# powerboard.net
KiCad netlist of a schematic drawn in EAGLE
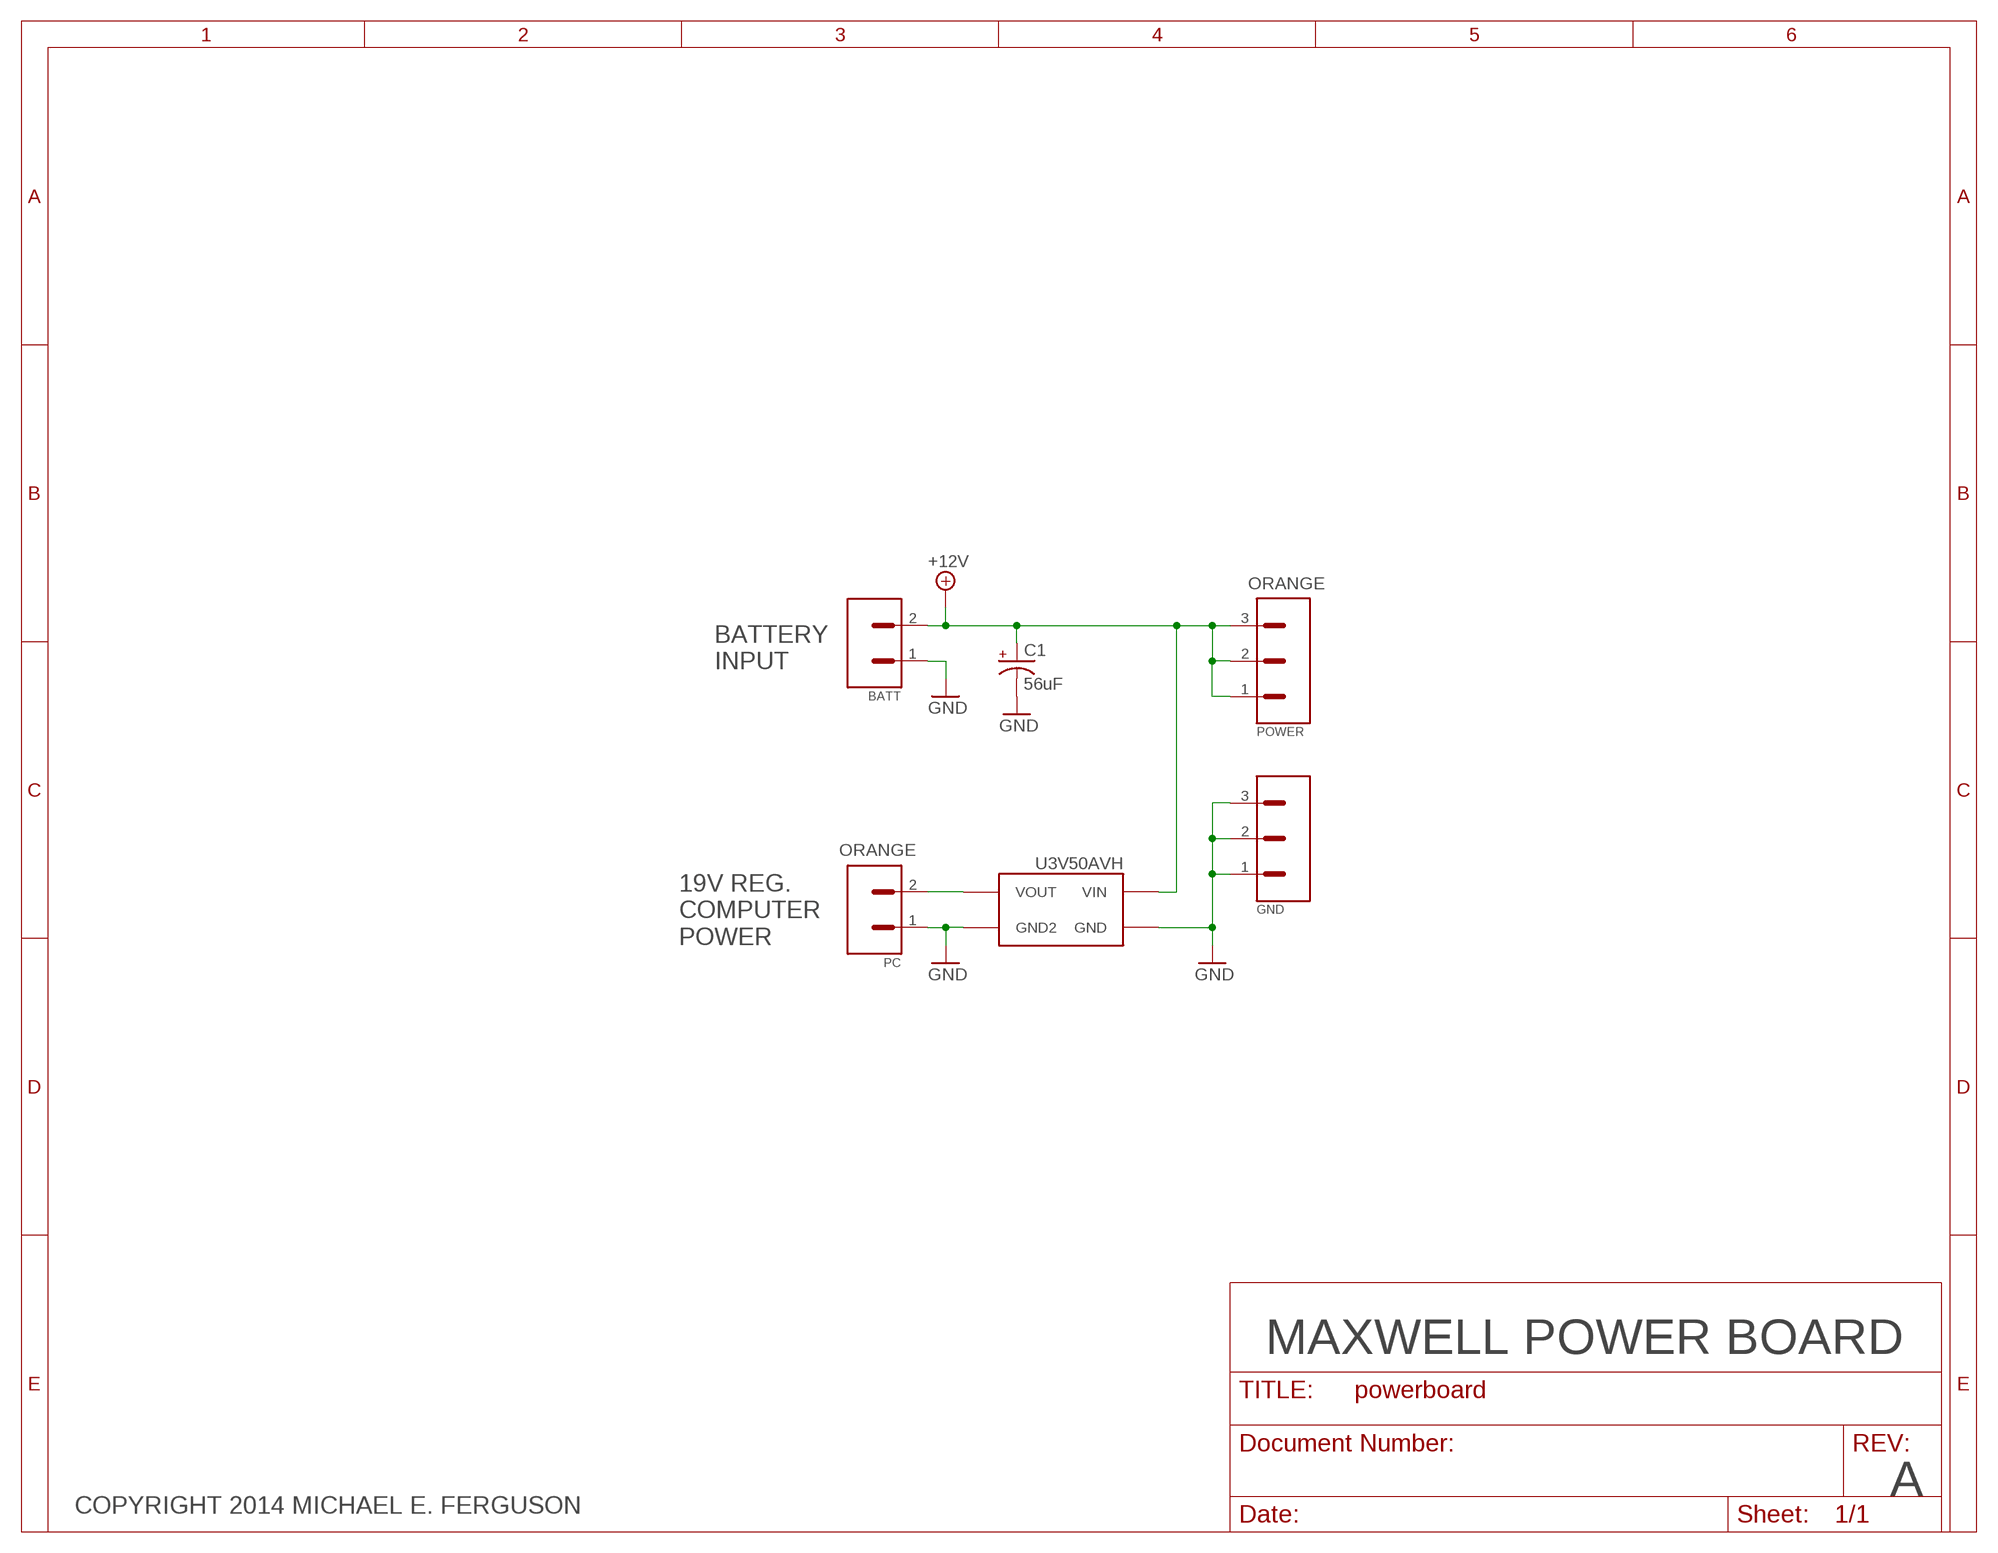
[diagram p0: schematic, sheet 1]

(export (version "E")
  (design (tool "Eeschema 10.0.6"))
  (components
    (comp (ref "BATT")
      (value "1760510000")
      (footprint "eagle-import:1760490000")
      (libsource (lib "eagle-import") (part "1760510000"))
    )
    (comp (ref "C1")
      (value "56uF")
      (footprint "eagle-import:OSCON_SVPF_6.3MM")
      (libsource (lib "eagle-import") (part "25SVPF56M"))
    )
    (comp (ref "GND")
      (value "1760520000")
      (footprint "eagle-import:1760520000")
      (libsource (lib "eagle-import") (part "1760520000"))
    )
    (comp (ref "PC")
      (value "1760490000")
      (footprint "eagle-import:1760490000")
      (libsource (lib "eagle-import") (part "1760490000"))
    )
    (comp (ref "POWER")
      (value "1760520000")
      (footprint "eagle-import:1760520000")
      (libsource (lib "eagle-import") (part "1760520000"))
    )
    (comp (ref "U3V50AVH")
      (value "U3V50AHV")
      (footprint "eagle-import:U3V50AHV")
      (libsource (lib "eagle-import") (part "U3V50AHV"))
    )
  )
  (nets
    (net (code "1") (name "+12V") (class "Default")
      (node (ref "BATT") (pin "2") (pinfunction "2_2") (pintype "bidirectional"))
      (node (ref "C1") (pin "+") (pinfunction "+_+") (pintype "passive"))
      (node (ref "POWER") (pin "1") (pinfunction "1_1") (pintype "bidirectional"))
      (node (ref "POWER") (pin "2") (pinfunction "2_2") (pintype "bidirectional"))
      (node (ref "POWER") (pin "3") (pinfunction "3_3") (pintype "bidirectional"))
      (node (ref "U3V50AVH") (pin "V_IN") (pinfunction "VIN_V_IN") (pintype "bidirectional"))
    )
    (net (code "2") (name "GND") (class "Default")
      (node (ref "BATT") (pin "1") (pinfunction "1_1") (pintype "bidirectional"))
      (node (ref "C1") (pin "-") (pinfunction "-_-") (pintype "passive"))
      (node (ref "GND") (pin "1") (pinfunction "1_1") (pintype "bidirectional"))
      (node (ref "GND") (pin "2") (pinfunction "2_2") (pintype "bidirectional"))
      (node (ref "GND") (pin "3") (pinfunction "3_3") (pintype "bidirectional"))
      (node (ref "PC") (pin "1") (pinfunction "1_1") (pintype "bidirectional"))
      (node (ref "U3V50AVH") (pin "GND_IN") (pinfunction "GND_GND_IN") (pintype "bidirectional"))
      (node (ref "U3V50AVH") (pin "GND_OUT") (pinfunction "GND2_GND_OUT") (pintype "bidirectional"))
    )
    (net (code "3") (name "Net-(U3V50AVH-VOUT)") (class "Default")
      (node (ref "PC") (pin "2") (pinfunction "2_2") (pintype "bidirectional"))
      (node (ref "U3V50AVH") (pin "V_OUT") (pinfunction "VOUT_V_OUT") (pintype "bidirectional"))
    )
  )
)
